# GrblMainboard_-_v2_2.net
KiCad netlist of a schematic drawn in EAGLE
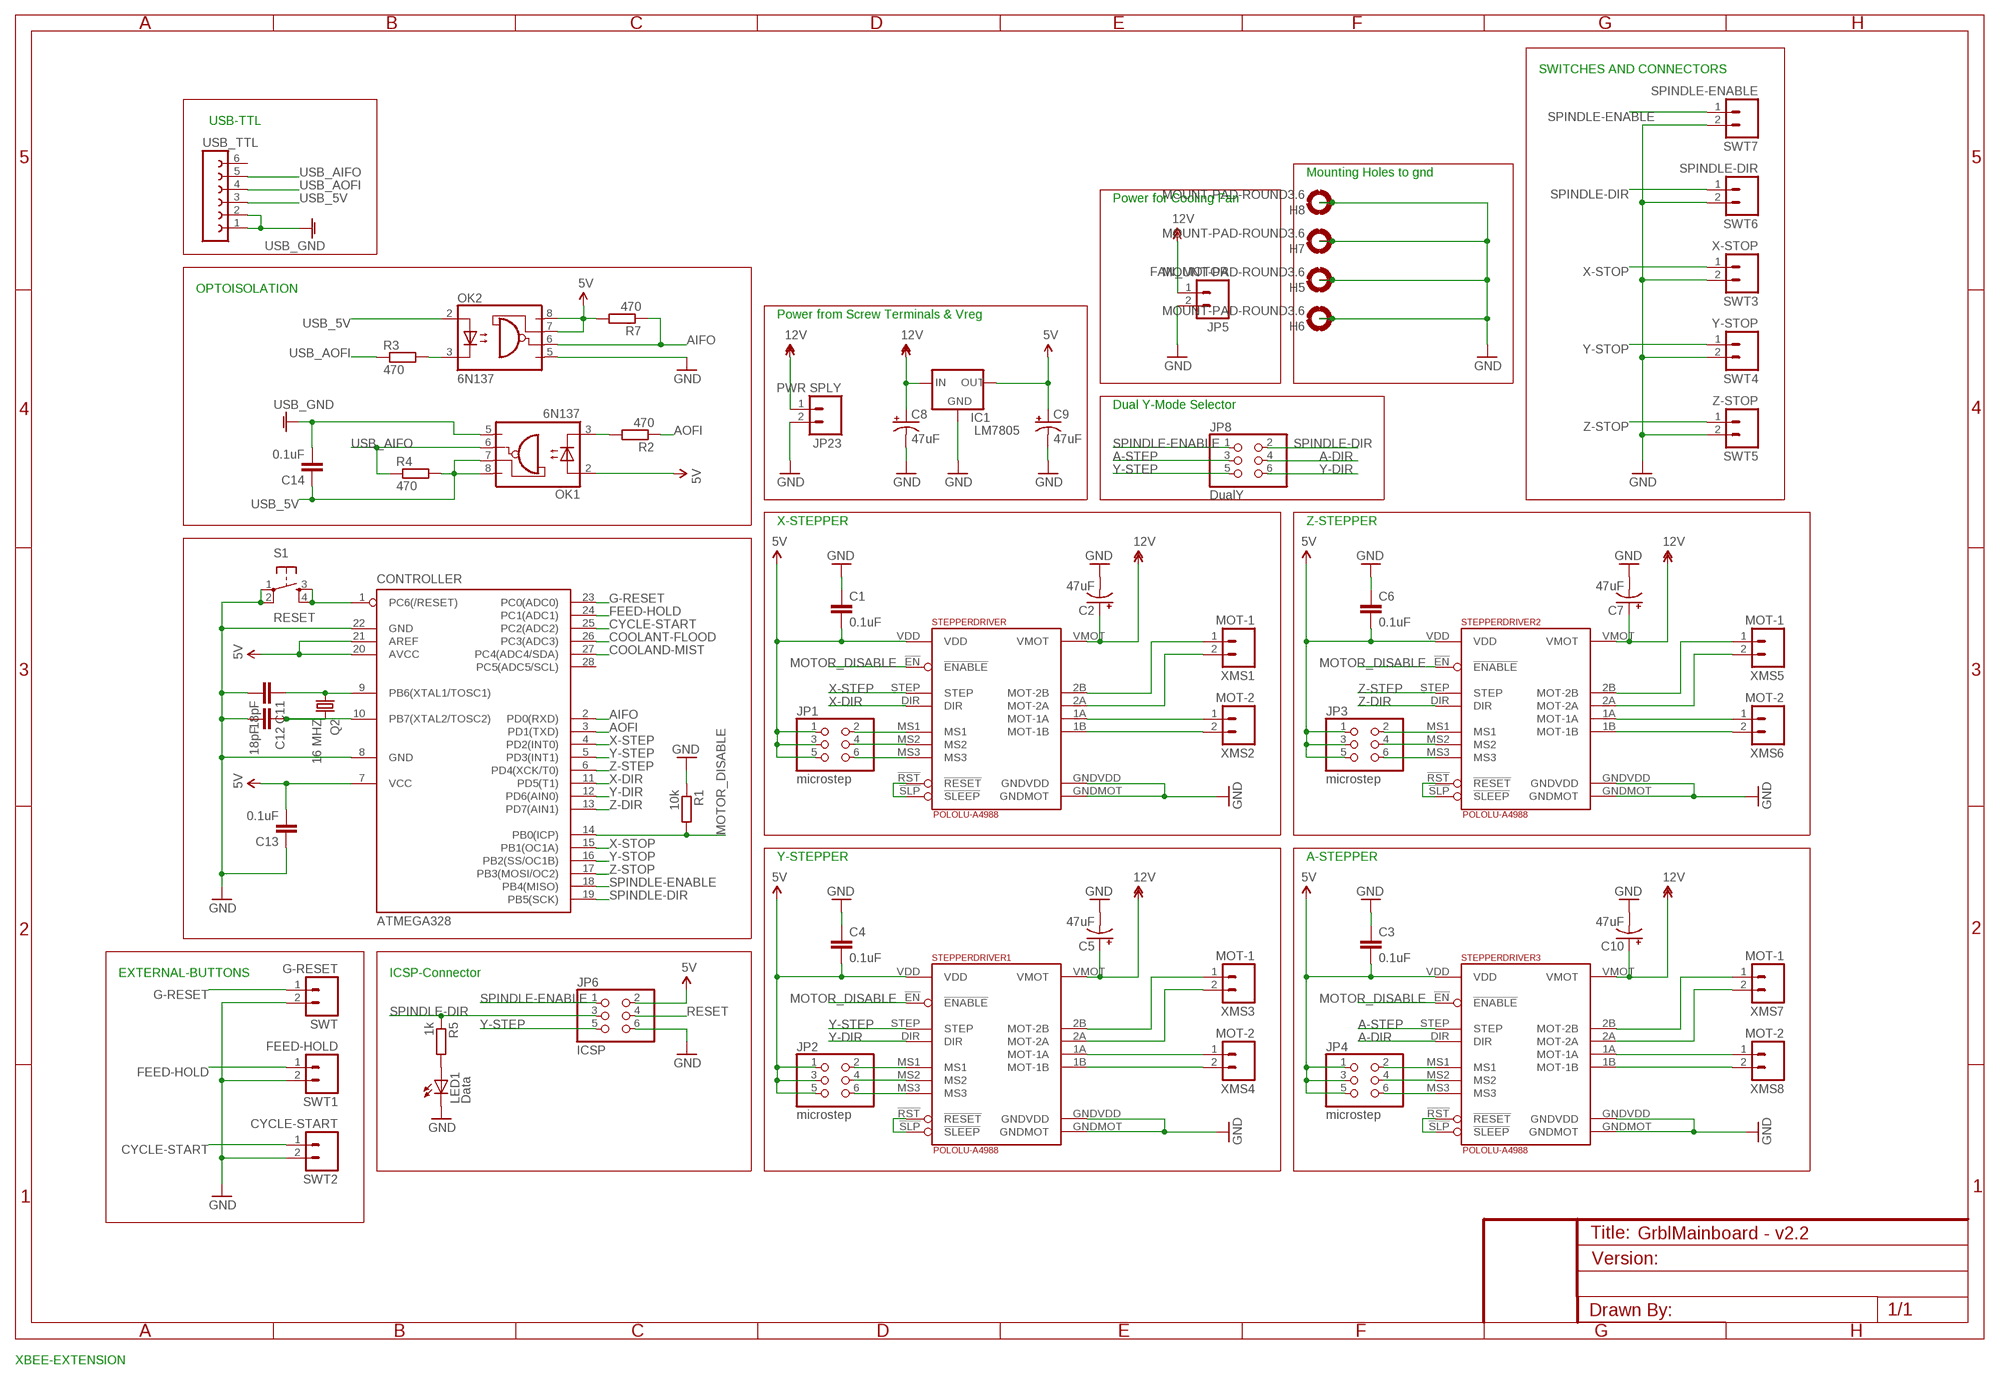
[diagram p0: schematic, sheet 1]

(export (version "E")
  (design (tool "Eeschema 10.0.6"))
  (components
    (comp (ref "ATMEGA328")
      (value "CONTROLLER")
      (footprint "eagle-import:DIL28-3")
      (libsource (lib "eagle-import") (part "MEGA8-P"))
    )
    (comp (ref "C1")
      (value "0.1uF")
      (footprint "eagle-import:C025-025X050")
      (libsource (lib "eagle-import") (part "C-EU025-025X050"))
    )
    (comp (ref "C2")
      (value "47uF")
      (footprint "eagle-import:E2,5-6")
      (libsource (lib "eagle-import") (part "CPOL-USE2.5-6"))
    )
    (comp (ref "C3")
      (value "0.1uF")
      (footprint "eagle-import:C025-025X050")
      (libsource (lib "eagle-import") (part "C-EU025-025X050"))
    )
    (comp (ref "C4")
      (value "0.1uF")
      (footprint "eagle-import:C025-025X050")
      (libsource (lib "eagle-import") (part "C-EU025-025X050"))
    )
    (comp (ref "C5")
      (value "47uF")
      (footprint "eagle-import:E2,5-6")
      (libsource (lib "eagle-import") (part "CPOL-USE2.5-6"))
    )
    (comp (ref "C6")
      (value "0.1uF")
      (footprint "eagle-import:C025-025X050")
      (libsource (lib "eagle-import") (part "C-EU025-025X050"))
    )
    (comp (ref "C7")
      (value "47uF")
      (footprint "eagle-import:E2,5-6")
      (libsource (lib "eagle-import") (part "CPOL-USE2.5-6"))
    )
    (comp (ref "C8")
      (value "47uF")
      (footprint "eagle-import:E2,5-6")
      (libsource (lib "eagle-import") (part "CPOL-USE2.5-6"))
    )
    (comp (ref "C9")
      (value "47uF")
      (footprint "eagle-import:E2,5-6")
      (libsource (lib "eagle-import") (part "CPOL-USE2.5-6"))
    )
    (comp (ref "C10")
      (value "47uF")
      (footprint "eagle-import:E2,5-6")
      (libsource (lib "eagle-import") (part "CPOL-USE2.5-6"))
    )
    (comp (ref "C11")
      (value "18pF")
      (footprint "eagle-import:CAP-PTH-SMALL2")
      (libsource (lib "eagle-import") (part "CAPPTH2"))
    )
    (comp (ref "C12")
      (value "18pF")
      (footprint "eagle-import:CAP-PTH-SMALL2")
      (libsource (lib "eagle-import") (part "CAPPTH2"))
    )
    (comp (ref "C13")
      (value "0.1uF")
      (footprint "eagle-import:CAP-PTH-SMALL2")
      (libsource (lib "eagle-import") (part "CAPPTH2"))
    )
    (comp (ref "C14")
      (value "0.1uF")
      (footprint "eagle-import:CAP-PTH-SMALL2")
      (libsource (lib "eagle-import") (part "CAPPTH2"))
    )
    (comp (ref "H5")
      (value "MOUNT-PAD-ROUND3.6")
      (footprint "eagle-import:3,6-PAD")
      (libsource (lib "eagle-import") (part "MOUNT-PAD-ROUND3.6"))
    )
    (comp (ref "H6")
      (value "MOUNT-PAD-ROUND3.6")
      (footprint "eagle-import:3,6-PAD")
      (libsource (lib "eagle-import") (part "MOUNT-PAD-ROUND3.6"))
    )
    (comp (ref "H7")
      (value "MOUNT-PAD-ROUND3.6")
      (footprint "eagle-import:3,6-PAD")
      (libsource (lib "eagle-import") (part "MOUNT-PAD-ROUND3.6"))
    )
    (comp (ref "H8")
      (value "MOUNT-PAD-ROUND3.6")
      (footprint "eagle-import:3,6-PAD")
      (libsource (lib "eagle-import") (part "MOUNT-PAD-ROUND3.6"))
    )
    (comp (ref "IC1")
      (value "LM7805")
      (footprint "eagle-import:78XXL-CUSTOM")
      (libsource (lib "eagle-import") (part "V_REG_78XX"))
    )
    (comp (ref "JP1")
      (value "microstep")
      (footprint "eagle-import:2X03")
      (libsource (lib "eagle-import") (part "PINHD-2X3"))
    )
    (comp (ref "JP2")
      (value "microstep")
      (footprint "eagle-import:2X03")
      (libsource (lib "eagle-import") (part "PINHD-2X3"))
    )
    (comp (ref "JP3")
      (value "microstep")
      (footprint "eagle-import:2X03")
      (libsource (lib "eagle-import") (part "PINHD-2X3"))
    )
    (comp (ref "JP4")
      (value "microstep")
      (footprint "eagle-import:2X03")
      (libsource (lib "eagle-import") (part "PINHD-2X3"))
    )
    (comp (ref "JP5")
      (value "FAN_MOTOR")
      (footprint "eagle-import:SCREWTERMINAL-5MM-2")
      (libsource (lib "eagle-import") (part "M025MM"))
    )
    (comp (ref "JP6")
      (value "ICSP")
      (footprint "eagle-import:2X03")
      (libsource (lib "eagle-import") (part "PINHD-2X3"))
    )
    (comp (ref "JP8")
      (value "DualY")
      (footprint "eagle-import:2X03")
      (libsource (lib "eagle-import") (part "PINHD-2X3"))
    )
    (comp (ref "JP23")
      (value "PWR SPLY")
      (footprint "eagle-import:SCREWTERMINAL-5MM-2")
      (libsource (lib "eagle-import") (part "M025MM"))
    )
    (comp (ref "LED1")
      (value "Data")
      (footprint "eagle-import:LED5MM")
      (libsource (lib "eagle-import") (part "LED5MM"))
    )
    (comp (ref "OK1")
      (value "6N137")
      (footprint "eagle-import:DIL08")
      (libsource (lib "eagle-import") (part "6N137"))
    )
    (comp (ref "OK2")
      (value "6N137")
      (footprint "eagle-import:DIL08")
      (libsource (lib "eagle-import") (part "6N137"))
    )
    (comp (ref "Q2")
      (value "16 MHZ")
      (footprint "eagle-import:HC49_S")
      (libsource (lib "eagle-import") (part "CRYSTALHC49S"))
    )
    (comp (ref "R1")
      (value "10k")
      (footprint "eagle-import:0207_10")
      (libsource (lib "eagle-import") (part "R-EU_0207/10"))
    )
    (comp (ref "R2")
      (value "470")
      (footprint "eagle-import:0207_12")
      (libsource (lib "eagle-import") (part "R-EU_0207/12"))
    )
    (comp (ref "R3")
      (value "470")
      (footprint "eagle-import:0207_12")
      (libsource (lib "eagle-import") (part "R-EU_0207/12"))
    )
    (comp (ref "R4")
      (value "470")
      (footprint "eagle-import:0207_12")
      (libsource (lib "eagle-import") (part "R-EU_0207/12"))
    )
    (comp (ref "R5")
      (value "1k")
      (footprint "eagle-import:0207_10")
      (libsource (lib "eagle-import") (part "R-EU_0207/10"))
    )
    (comp (ref "R7")
      (value "470")
      (footprint "eagle-import:0207_12")
      (libsource (lib "eagle-import") (part "R-EU_0207/12"))
    )
    (comp (ref "S1")
      (value "RESET")
      (footprint "eagle-import:TACTILE-PTH")
      (libsource (lib "eagle-import") (part "TAC_SWITCHPTH"))
    )
    (comp (ref "STEPPERDRIVER")
      (value "POLOLU-A4988")
      (footprint "eagle-import:POLOLU-ALLEGRO-PTH")
      (libsource (lib "eagle-import") (part "POLOLU-ALLEGRO"))
    )
    (comp (ref "STEPPERDRIVER1")
      (value "POLOLU-A4988")
      (footprint "eagle-import:POLOLU-ALLEGRO-PTH")
      (libsource (lib "eagle-import") (part "POLOLU-ALLEGRO"))
    )
    (comp (ref "STEPPERDRIVER2")
      (value "POLOLU-A4988")
      (footprint "eagle-import:POLOLU-ALLEGRO-PTH")
      (libsource (lib "eagle-import") (part "POLOLU-ALLEGRO"))
    )
    (comp (ref "STEPPERDRIVER3")
      (value "POLOLU-A4988")
      (footprint "eagle-import:POLOLU-ALLEGRO-PTH")
      (libsource (lib "eagle-import") (part "POLOLU-ALLEGRO"))
    )
    (comp (ref "SWT")
      (value "G-RESET")
      (footprint "eagle-import:SCREWTERMINAL-5MM-2")
      (libsource (lib "eagle-import") (part "M025MM"))
    )
    (comp (ref "SWT1")
      (value "FEED-HOLD")
      (footprint "eagle-import:SCREWTERMINAL-5MM-2")
      (libsource (lib "eagle-import") (part "M025MM"))
    )
    (comp (ref "SWT2")
      (value "CYCLE-START")
      (footprint "eagle-import:SCREWTERMINAL-5MM-2")
      (libsource (lib "eagle-import") (part "M025MM"))
    )
    (comp (ref "SWT3")
      (value "X-STOP")
      (footprint "eagle-import:SCREWTERMINAL-5MM-2")
      (libsource (lib "eagle-import") (part "M025MM"))
    )
    (comp (ref "SWT4")
      (value "Y-STOP")
      (footprint "eagle-import:SCREWTERMINAL-5MM-2")
      (libsource (lib "eagle-import") (part "M025MM"))
    )
    (comp (ref "SWT5")
      (value "Z-STOP")
      (footprint "eagle-import:SCREWTERMINAL-5MM-2")
      (libsource (lib "eagle-import") (part "M025MM"))
    )
    (comp (ref "SWT6")
      (value "SPINDLE-DIR")
      (footprint "eagle-import:SCREWTERMINAL-5MM-2")
      (libsource (lib "eagle-import") (part "M025MM"))
    )
    (comp (ref "SWT7")
      (value "SPINDLE-ENABLE")
      (footprint "eagle-import:SCREWTERMINAL-5MM-2")
      (libsource (lib "eagle-import") (part "M025MM"))
    )
    (comp (ref "USB_TTL")
      (value "FE06-1")
      (footprint "eagle-import:FE06")
      (libsource (lib "eagle-import") (part "FE06-1"))
    )
    (comp (ref "XMS1")
      (value "MOT-1")
      (footprint "eagle-import:SCREWTERMINAL-5MM-2")
      (libsource (lib "eagle-import") (part "M025MM"))
    )
    (comp (ref "XMS2")
      (value "MOT-2")
      (footprint "eagle-import:SCREWTERMINAL-5MM-2")
      (libsource (lib "eagle-import") (part "M025MM"))
    )
    (comp (ref "XMS3")
      (value "MOT-1")
      (footprint "eagle-import:SCREWTERMINAL-5MM-2")
      (libsource (lib "eagle-import") (part "M025MM"))
    )
    (comp (ref "XMS4")
      (value "MOT-2")
      (footprint "eagle-import:SCREWTERMINAL-5MM-2")
      (libsource (lib "eagle-import") (part "M025MM"))
    )
    (comp (ref "XMS5")
      (value "MOT-1")
      (footprint "eagle-import:SCREWTERMINAL-5MM-2")
      (libsource (lib "eagle-import") (part "M025MM"))
    )
    (comp (ref "XMS6")
      (value "MOT-2")
      (footprint "eagle-import:SCREWTERMINAL-5MM-2")
      (libsource (lib "eagle-import") (part "M025MM"))
    )
    (comp (ref "XMS7")
      (value "MOT-1")
      (footprint "eagle-import:SCREWTERMINAL-5MM-2")
      (libsource (lib "eagle-import") (part "M025MM"))
    )
    (comp (ref "XMS8")
      (value "MOT-2")
      (footprint "eagle-import:SCREWTERMINAL-5MM-2")
      (libsource (lib "eagle-import") (part "M025MM"))
    )
  )
  (nets
    (net (code "1") (name "/A-DIR") (class "Default")
      (node (ref "JP8") (pin "4") (pinfunction "4_4") (pintype "passive"))
      (node (ref "STEPPERDRIVER3") (pin "DIR") (pinfunction "DIR_DIR") (pintype "bidirectional"))
    )
    (net (code "2") (name "/A-STEP") (class "Default")
      (node (ref "JP8") (pin "3") (pinfunction "3_3") (pintype "passive"))
      (node (ref "STEPPERDRIVER3") (pin "STEP") (pinfunction "STEP_STEP") (pintype "bidirectional"))
    )
    (net (code "3") (name "/AIFO") (class "Default")
      (node (ref "ATMEGA328") (pin "2") (pinfunction "PD0(RXD)_2") (pintype "bidirectional"))
      (node (ref "OK2") (pin "6") (pinfunction "VO_6") (pintype "passive"))
      (node (ref "R7") (pin "1") (pinfunction "1_1") (pintype "passive"))
    )
    (net (code "4") (name "/AOFI") (class "Default")
      (node (ref "ATMEGA328") (pin "3") (pinfunction "PD1(TXD)_3") (pintype "bidirectional"))
      (node (ref "R2") (pin "1") (pinfunction "1_1") (pintype "passive"))
    )
    (net (code "5") (name "/COOLAND-MIST") (class "Default")
      (node (ref "ATMEGA328") (pin "27") (pinfunction "PC4(ADC4/SDA)_27") (pintype "bidirectional"))
    )
    (net (code "6") (name "/COOLANT-FLOOD") (class "Default")
      (node (ref "ATMEGA328") (pin "26") (pinfunction "PC3(ADC3)_26") (pintype "bidirectional"))
    )
    (net (code "7") (name "/CYCLE-START") (class "Default")
      (node (ref "ATMEGA328") (pin "25") (pinfunction "PC2(ADC2)_25") (pintype "bidirectional"))
      (node (ref "SWT2") (pin "1") (pinfunction "1_1") (pintype "passive"))
    )
    (net (code "8") (name "/FEED-HOLD") (class "Default")
      (node (ref "ATMEGA328") (pin "24") (pinfunction "PC1(ADC1)_24") (pintype "bidirectional"))
      (node (ref "SWT1") (pin "1") (pinfunction "1_1") (pintype "passive"))
    )
    (net (code "9") (name "/G-RESET") (class "Default")
      (node (ref "ATMEGA328") (pin "23") (pinfunction "PC0(ADC0)_23") (pintype "bidirectional"))
      (node (ref "SWT") (pin "1") (pinfunction "1_1") (pintype "passive"))
    )
    (net (code "10") (name "/MOTOR_DISABLE") (class "Default")
      (node (ref "ATMEGA328") (pin "14") (pinfunction "PB0(ICP)_14") (pintype "bidirectional"))
      (node (ref "R1") (pin "2") (pinfunction "2_2") (pintype "passive"))
      (node (ref "STEPPERDRIVER") (pin "!EN") (pinfunction "~{ENABLE}_!EN") (pintype "input"))
      (node (ref "STEPPERDRIVER1") (pin "!EN") (pinfunction "~{ENABLE}_!EN") (pintype "input"))
      (node (ref "STEPPERDRIVER2") (pin "!EN") (pinfunction "~{ENABLE}_!EN") (pintype "input"))
      (node (ref "STEPPERDRIVER3") (pin "!EN") (pinfunction "~{ENABLE}_!EN") (pintype "input"))
    )
    (net (code "11") (name "/RESET") (class "Default")
      (node (ref "ATMEGA328") (pin "1") (pinfunction "PC6(/RESET)_1") (pintype "bidirectional"))
      (node (ref "JP6") (pin "4") (pinfunction "4_4") (pintype "passive"))
      (node (ref "S1") (pin "3") (pinfunction "3_3") (pintype "passive"))
      (node (ref "S1") (pin "4") (pinfunction "4_4") (pintype "passive"))
    )
    (net (code "12") (name "/SPINDLE-DIR") (class "Default")
      (node (ref "ATMEGA328") (pin "19") (pinfunction "PB5(SCK)_19") (pintype "bidirectional"))
      (node (ref "JP6") (pin "3") (pinfunction "3_3") (pintype "passive"))
      (node (ref "JP8") (pin "2") (pinfunction "2_2") (pintype "passive"))
      (node (ref "R5") (pin "1") (pinfunction "1_1") (pintype "passive"))
      (node (ref "SWT6") (pin "1") (pinfunction "1_1") (pintype "passive"))
    )
    (net (code "13") (name "/SPINDLE-ENABLE") (class "Default")
      (node (ref "ATMEGA328") (pin "18") (pinfunction "PB4(MISO)_18") (pintype "bidirectional"))
      (node (ref "JP6") (pin "1") (pinfunction "1_1") (pintype "passive"))
      (node (ref "JP8") (pin "1") (pinfunction "1_1") (pintype "passive"))
      (node (ref "SWT7") (pin "1") (pinfunction "1_1") (pintype "passive"))
    )
    (net (code "14") (name "/USB_5V") (class "Default")
      (node (ref "C14") (pin "1") (pinfunction "1_1") (pintype "passive"))
      (node (ref "OK1") (pin "7") (pinfunction "VE_7") (pintype "passive"))
      (node (ref "OK1") (pin "8") (pinfunction "VCC_8") (pintype "passive"))
      (node (ref "OK2") (pin "2") (pinfunction "A_2") (pintype "passive"))
      (node (ref "R4") (pin "2") (pinfunction "2_2") (pintype "passive"))
      (node (ref "USB_TTL") (pin "3") (pinfunction "3_3") (pintype "passive"))
    )
    (net (code "15") (name "/USB_AIFO") (class "Default")
      (node (ref "OK1") (pin "6") (pinfunction "VO_6") (pintype "passive"))
      (node (ref "R4") (pin "1") (pinfunction "1_1") (pintype "passive"))
      (node (ref "USB_TTL") (pin "5") (pinfunction "5_5") (pintype "passive"))
    )
    (net (code "16") (name "/USB_AOFI") (class "Default")
      (node (ref "R3") (pin "1") (pinfunction "1_1") (pintype "passive"))
      (node (ref "USB_TTL") (pin "4") (pinfunction "4_4") (pintype "passive"))
    )
    (net (code "17") (name "/X-DIR") (class "Default")
      (node (ref "ATMEGA328") (pin "11") (pinfunction "PD5(T1)_11") (pintype "bidirectional"))
      (node (ref "STEPPERDRIVER") (pin "DIR") (pinfunction "DIR_DIR") (pintype "bidirectional"))
    )
    (net (code "18") (name "/X-STEP") (class "Default")
      (node (ref "ATMEGA328") (pin "4") (pinfunction "PD2(INT0)_4") (pintype "bidirectional"))
      (node (ref "STEPPERDRIVER") (pin "STEP") (pinfunction "STEP_STEP") (pintype "bidirectional"))
    )
    (net (code "19") (name "/X-STOP") (class "Default")
      (node (ref "ATMEGA328") (pin "15") (pinfunction "PB1(OC1A)_15") (pintype "bidirectional"))
      (node (ref "SWT3") (pin "1") (pinfunction "1_1") (pintype "passive"))
    )
    (net (code "20") (name "/Y-DIR") (class "Default")
      (node (ref "ATMEGA328") (pin "12") (pinfunction "PD6(AIN0)_12") (pintype "bidirectional"))
      (node (ref "JP8") (pin "6") (pinfunction "6_6") (pintype "passive"))
      (node (ref "STEPPERDRIVER1") (pin "DIR") (pinfunction "DIR_DIR") (pintype "bidirectional"))
    )
    (net (code "21") (name "/Y-STEP") (class "Default")
      (node (ref "ATMEGA328") (pin "5") (pinfunction "PD3(INT1)_5") (pintype "bidirectional"))
      (node (ref "JP6") (pin "5") (pinfunction "5_5") (pintype "passive"))
      (node (ref "JP8") (pin "5") (pinfunction "5_5") (pintype "passive"))
      (node (ref "STEPPERDRIVER1") (pin "STEP") (pinfunction "STEP_STEP") (pintype "bidirectional"))
    )
    (net (code "22") (name "/Y-STOP") (class "Default")
      (node (ref "ATMEGA328") (pin "16") (pinfunction "PB2(SS/OC1B)_16") (pintype "bidirectional"))
      (node (ref "SWT4") (pin "1") (pinfunction "1_1") (pintype "passive"))
    )
    (net (code "23") (name "/Z-DIR") (class "Default")
      (node (ref "ATMEGA328") (pin "13") (pinfunction "PD7(AIN1)_13") (pintype "bidirectional"))
      (node (ref "STEPPERDRIVER2") (pin "DIR") (pinfunction "DIR_DIR") (pintype "bidirectional"))
    )
    (net (code "24") (name "/Z-STEP") (class "Default")
      (node (ref "ATMEGA328") (pin "6") (pinfunction "PD4(XCK/T0)_6") (pintype "bidirectional"))
      (node (ref "STEPPERDRIVER2") (pin "STEP") (pinfunction "STEP_STEP") (pintype "bidirectional"))
    )
    (net (code "25") (name "/Z-STOP") (class "Default")
      (node (ref "ATMEGA328") (pin "17") (pinfunction "PB3(MOSI/OC2)_17") (pintype "bidirectional"))
      (node (ref "SWT5") (pin "1") (pinfunction "1_1") (pintype "passive"))
    )
    (net (code "26") (name "5V") (class "Default")
      (node (ref "ATMEGA328") (pin "20") (pinfunction "AVCC_20") (pintype "power_in"))
      (node (ref "ATMEGA328") (pin "21") (pinfunction "AREF_21") (pintype "passive"))
      (node (ref "ATMEGA328") (pin "7") (pinfunction "VCC_7") (pintype "power_in"))
      (node (ref "C1") (pin "2") (pinfunction "2_2") (pintype "passive"))
      (node (ref "C13") (pin "2") (pinfunction "2_2") (pintype "passive"))
      (node (ref "C3") (pin "2") (pinfunction "2_2") (pintype "passive"))
      (node (ref "C4") (pin "2") (pinfunction "2_2") (pintype "passive"))
      (node (ref "C6") (pin "2") (pinfunction "2_2") (pintype "passive"))
      (node (ref "C9") (pin "+") (pinfunction "+_+") (pintype "passive"))
      (node (ref "IC1") (pin "OUT") (pinfunction "OUT_OUT") (pintype "output"))
      (node (ref "JP1") (pin "1") (pinfunction "1_1") (pintype "passive"))
      (node (ref "JP1") (pin "3") (pinfunction "3_3") (pintype "passive"))
      (node (ref "JP1") (pin "5") (pinfunction "5_5") (pintype "passive"))
      (node (ref "JP2") (pin "1") (pinfunction "1_1") (pintype "passive"))
      (node (ref "JP2") (pin "3") (pinfunction "3_3") (pintype "passive"))
      (node (ref "JP2") (pin "5") (pinfunction "5_5") (pintype "passive"))
      (node (ref "JP3") (pin "1") (pinfunction "1_1") (pintype "passive"))
      (node (ref "JP3") (pin "3") (pinfunction "3_3") (pintype "passive"))
      (node (ref "JP3") (pin "5") (pinfunction "5_5") (pintype "passive"))
      (node (ref "JP4") (pin "1") (pinfunction "1_1") (pintype "passive"))
      (node (ref "JP4") (pin "3") (pinfunction "3_3") (pintype "passive"))
      (node (ref "JP4") (pin "5") (pinfunction "5_5") (pintype "passive"))
      (node (ref "JP6") (pin "2") (pinfunction "2_2") (pintype "passive"))
      (node (ref "OK1") (pin "2") (pinfunction "A_2") (pintype "passive"))
      (node (ref "OK2") (pin "7") (pinfunction "VE_7") (pintype "passive"))
      (node (ref "OK2") (pin "8") (pinfunction "VCC_8") (pintype "passive"))
      (node (ref "R7") (pin "2") (pinfunction "2_2") (pintype "passive"))
      (node (ref "STEPPERDRIVER") (pin "VDD") (pinfunction "VDD_VDD") (pintype "power_in"))
      (node (ref "STEPPERDRIVER1") (pin "VDD") (pinfunction "VDD_VDD") (pintype "power_in"))
      (node (ref "STEPPERDRIVER2") (pin "VDD") (pinfunction "VDD_VDD") (pintype "power_in"))
      (node (ref "STEPPERDRIVER3") (pin "VDD") (pinfunction "VDD_VDD") (pintype "power_in"))
    )
    (net (code "27") (name "12V") (class "Default")
      (node (ref "C10") (pin "+") (pinfunction "+_+") (pintype "passive"))
      (node (ref "C2") (pin "+") (pinfunction "+_+") (pintype "passive"))
      (node (ref "C5") (pin "+") (pinfunction "+_+") (pintype "passive"))
      (node (ref "C7") (pin "+") (pinfunction "+_+") (pintype "passive"))
      (node (ref "C8") (pin "+") (pinfunction "+_+") (pintype "passive"))
      (node (ref "IC1") (pin "IN") (pinfunction "IN_IN") (pintype "input"))
      (node (ref "JP23") (pin "1") (pinfunction "1_1") (pintype "passive"))
      (node (ref "JP5") (pin "1") (pinfunction "1_1") (pintype "passive"))
      (node (ref "STEPPERDRIVER") (pin "VMOT") (pinfunction "VMOT_VMOT") (pintype "power_in"))
      (node (ref "STEPPERDRIVER1") (pin "VMOT") (pinfunction "VMOT_VMOT") (pintype "power_in"))
      (node (ref "STEPPERDRIVER2") (pin "VMOT") (pinfunction "VMOT_VMOT") (pintype "power_in"))
      (node (ref "STEPPERDRIVER3") (pin "VMOT") (pinfunction "VMOT_VMOT") (pintype "power_in"))
    )
    (net (code "28") (name "GND") (class "Default")
      (node (ref "ATMEGA328") (pin "22") (pinfunction "GND_22") (pintype "power_in"))
      (node (ref "ATMEGA328") (pin "8") (pinfunction "GND_8") (pintype "power_in"))
      (node (ref "C1") (pin "1") (pinfunction "1_1") (pintype "passive"))
      (node (ref "C10") (pin "-") (pinfunction "-_-") (pintype "passive"))
      (node (ref "C11") (pin "2") (pinfunction "2_2") (pintype "passive"))
      (node (ref "C12") (pin "2") (pinfunction "2_2") (pintype "passive"))
      (node (ref "C13") (pin "1") (pinfunction "1_1") (pintype "passive"))
      (node (ref "C2") (pin "-") (pinfunction "-_-") (pintype "passive"))
      (node (ref "C3") (pin "1") (pinfunction "1_1") (pintype "passive"))
      (node (ref "C4") (pin "1") (pinfunction "1_1") (pintype "passive"))
      (node (ref "C5") (pin "-") (pinfunction "-_-") (pintype "passive"))
      (node (ref "C6") (pin "1") (pinfunction "1_1") (pintype "passive"))
      (node (ref "C7") (pin "-") (pinfunction "-_-") (pintype "passive"))
      (node (ref "C8") (pin "-") (pinfunction "-_-") (pintype "passive"))
      (node (ref "C9") (pin "-") (pinfunction "-_-") (pintype "passive"))
      (node (ref "H5") (pin "B3,6") (pinfunction "MOUNT_B3,6") (pintype "passive"))
      (node (ref "H6") (pin "B3,6") (pinfunction "MOUNT_B3,6") (pintype "passive"))
      (node (ref "H7") (pin "B3,6") (pinfunction "MOUNT_B3,6") (pintype "passive"))
      (node (ref "H8") (pin "B3,6") (pinfunction "MOUNT_B3,6") (pintype "passive"))
      (node (ref "IC1") (pin "GND") (pinfunction "GND_GND") (pintype "input"))
      (node (ref "JP23") (pin "2") (pinfunction "2_2") (pintype "passive"))
      (node (ref "JP5") (pin "2") (pinfunction "2_2") (pintype "passive"))
      (node (ref "JP6") (pin "6") (pinfunction "6_6") (pintype "passive"))
      (node (ref "LED1") (pin "K") (pinfunction "C_K") (pintype "passive"))
      (node (ref "OK2") (pin "5") (pinfunction "GND_5") (pintype "passive"))
      (node (ref "R1") (pin "1") (pinfunction "1_1") (pintype "passive"))
      (node (ref "S1") (pin "1") (pinfunction "1_1") (pintype "passive"))
      (node (ref "S1") (pin "2") (pinfunction "2_2") (pintype "passive"))
      (node (ref "STEPPERDRIVER") (pin "GNDMOT") (pinfunction "GNDMOT_GNDMOT") (pintype "power_in"))
      (node (ref "STEPPERDRIVER") (pin "GNDVDD") (pinfunction "GNDVDD_GNDVDD") (pintype "power_in"))
      (node (ref "STEPPERDRIVER1") (pin "GNDMOT") (pinfunction "GNDMOT_GNDMOT") (pintype "power_in"))
      (node (ref "STEPPERDRIVER1") (pin "GNDVDD") (pinfunction "GNDVDD_GNDVDD") (pintype "power_in"))
      (node (ref "STEPPERDRIVER2") (pin "GNDMOT") (pinfunction "GNDMOT_GNDMOT") (pintype "power_in"))
      (node (ref "STEPPERDRIVER2") (pin "GNDVDD") (pinfunction "GNDVDD_GNDVDD") (pintype "power_in"))
      (node (ref "STEPPERDRIVER3") (pin "GNDMOT") (pinfunction "GNDMOT_GNDMOT") (pintype "power_in"))
      (node (ref "STEPPERDRIVER3") (pin "GNDVDD") (pinfunction "GNDVDD_GNDVDD") (pintype "power_in"))
      (node (ref "SWT") (pin "2") (pinfunction "2_2") (pintype "passive"))
      (node (ref "SWT1") (pin "2") (pinfunction "2_2") (pintype "passive"))
      (node (ref "SWT2") (pin "2") (pinfunction "2_2") (pintype "passive"))
      (node (ref "SWT3") (pin "2") (pinfunction "2_2") (pintype "passive"))
      (node (ref "SWT4") (pin "2") (pinfunction "2_2") (pintype "passive"))
      (node (ref "SWT5") (pin "2") (pinfunction "2_2") (pintype "passive"))
      (node (ref "SWT6") (pin "2") (pinfunction "2_2") (pintype "passive"))
      (node (ref "SWT7") (pin "2") (pinfunction "2_2") (pintype "passive"))
    )
    (net (code "29") (name "Net-(ATMEGA328-PB6(XTAL1{slash}TOSC1))") (class "Default")
      (node (ref "ATMEGA328") (pin "9") (pinfunction "PB6(XTAL1/TOSC1)_9") (pintype "bidirectional"))
      (node (ref "C11") (pin "1") (pinfunction "1_1") (pintype "passive"))
      (node (ref "Q2") (pin "1") (pinfunction "1_1") (pintype "passive"))
    )
    (net (code "30") (name "Net-(ATMEGA328-PB7(XTAL2{slash}TOSC2))") (class "Default")
      (node (ref "ATMEGA328") (pin "10") (pinfunction "PB7(XTAL2/TOSC2)_10") (pintype "bidirectional"))
      (node (ref "C12") (pin "1") (pinfunction "1_1") (pintype "passive"))
      (node (ref "Q2") (pin "2") (pinfunction "2_2") (pintype "passive"))
    )
    (net (code "31") (name "Net-(JP1-Pad2)") (class "Default")
      (node (ref "JP1") (pin "2") (pinfunction "2_2") (pintype "passive"))
      (node (ref "STEPPERDRIVER") (pin "MS1") (pinfunction "MS1_MS1") (pintype "input"))
    )
    (net (code "32") (name "Net-(JP1-Pad4)") (class "Default")
      (node (ref "JP1") (pin "4") (pinfunction "4_4") (pintype "passive"))
      (node (ref "STEPPERDRIVER") (pin "MS2") (pinfunction "MS2_MS2") (pintype "input"))
    )
    (net (code "33") (name "Net-(JP1-Pad6)") (class "Default")
      (node (ref "JP1") (pin "6") (pinfunction "6_6") (pintype "passive"))
      (node (ref "STEPPERDRIVER") (pin "MS3") (pinfunction "MS3_MS3") (pintype "input"))
    )
    (net (code "34") (name "Net-(JP2-Pad2)") (class "Default")
      (node (ref "JP2") (pin "2") (pinfunction "2_2") (pintype "passive"))
      (node (ref "STEPPERDRIVER1") (pin "MS1") (pinfunction "MS1_MS1") (pintype "input"))
    )
    (net (code "35") (name "Net-(JP2-Pad4)") (class "Default")
      (node (ref "JP2") (pin "4") (pinfunction "4_4") (pintype "passive"))
      (node (ref "STEPPERDRIVER1") (pin "MS2") (pinfunction "MS2_MS2") (pintype "input"))
    )
    (net (code "36") (name "Net-(JP2-Pad6)") (class "Default")
      (node (ref "JP2") (pin "6") (pinfunction "6_6") (pintype "passive"))
      (node (ref "STEPPERDRIVER1") (pin "MS3") (pinfunction "MS3_MS3") (pintype "input"))
    )
    (net (code "37") (name "Net-(JP3-Pad2)") (class "Default")
      (node (ref "JP3") (pin "2") (pinfunction "2_2") (pintype "passive"))
      (node (ref "STEPPERDRIVER2") (pin "MS1") (pinfunction "MS1_MS1") (pintype "input"))
    )
    (net (code "38") (name "Net-(JP3-Pad4)") (class "Default")
      (node (ref "JP3") (pin "4") (pinfunction "4_4") (pintype "passive"))
      (node (ref "STEPPERDRIVER2") (pin "MS2") (pinfunction "MS2_MS2") (pintype "input"))
    )
    (net (code "39") (name "Net-(JP3-Pad6)") (class "Default")
      (node (ref "JP3") (pin "6") (pinfunction "6_6") (pintype "passive"))
      (node (ref "STEPPERDRIVER2") (pin "MS3") (pinfunction "MS3_MS3") (pintype "input"))
    )
    (net (code "40") (name "Net-(JP4-Pad2)") (class "Default")
      (node (ref "JP4") (pin "2") (pinfunction "2_2") (pintype "passive"))
      (node (ref "STEPPERDRIVER3") (pin "MS1") (pinfunction "MS1_MS1") (pintype "input"))
    )
    (net (code "41") (name "Net-(JP4-Pad4)") (class "Default")
      (node (ref "JP4") (pin "4") (pinfunction "4_4") (pintype "passive"))
      (node (ref "STEPPERDRIVER3") (pin "MS2") (pinfunction "MS2_MS2") (pintype "input"))
    )
    (net (code "42") (name "Net-(JP4-Pad6)") (class "Default")
      (node (ref "JP4") (pin "6") (pinfunction "6_6") (pintype "passive"))
      (node (ref "STEPPERDRIVER3") (pin "MS3") (pinfunction "MS3_MS3") (pintype "input"))
    )
    (net (code "43") (name "Net-(LED1-PadA)") (class "Default")
      (node (ref "LED1") (pin "A") (pinfunction "A_A") (pintype "passive"))
      (node (ref "R5") (pin "2") (pinfunction "2_2") (pintype "passive"))
    )
    (net (code "44") (name "Net-(OK1-C)") (class "Default")
      (node (ref "OK1") (pin "3") (pinfunction "C_3") (pintype "passive"))
      (node (ref "R2") (pin "2") (pinfunction "2_2") (pintype "passive"))
    )
    (net (code "45") (name "Net-(OK2-C)") (class "Default")
      (node (ref "OK2") (pin "3") (pinfunction "C_3") (pintype "passive"))
      (node (ref "R3") (pin "2") (pinfunction "2_2") (pintype "passive"))
    )
    (net (code "46") (name "Net-(STEPPERDRIVER-MOT-1A)") (class "Default")
      (node (ref "STEPPERDRIVER") (pin "1A") (pinfunction "MOT-1A_1A") (pintype "power_in"))
      (node (ref "XMS2") (pin "1") (pinfunction "1_1") (pintype "passive"))
    )
    (net (code "47") (name "Net-(STEPPERDRIVER-MOT-1B)") (class "Default")
      (node (ref "STEPPERDRIVER") (pin "1B") (pinfunction "MOT-1B_1B") (pintype "power_in"))
      (node (ref "XMS2") (pin "2") (pinfunction "2_2") (pintype "passive"))
    )
    (net (code "48") (name "Net-(STEPPERDRIVER-MOT-2A)") (class "Default")
      (node (ref "STEPPERDRIVER") (pin "2A") (pinfunction "MOT-2A_2A") (pintype "power_in"))
      (node (ref "XMS1") (pin "2") (pinfunction "2_2") (pintype "passive"))
    )
    (net (code "49") (name "Net-(STEPPERDRIVER-MOT-2B)") (class "Default")
      (node (ref "STEPPERDRIVER") (pin "2B") (pinfunction "MOT-2B_2B") (pintype "power_in"))
      (node (ref "XMS1") (pin "1") (pinfunction "1_1") (pintype "passive"))
    )
    (net (code "50") (name "Net-(STEPPERDRIVER-~{RESET})") (class "Default")
      (node (ref "STEPPERDRIVER") (pin "!RST") (pinfunction "~{RESET}_!RST") (pintype "input"))
      (node (ref "STEPPERDRIVER") (pin "!SLP") (pinfunction "~{SLEEP}_!SLP") (pintype "input"))
    )
    (net (code "51") (name "Net-(STEPPERDRIVER1-MOT-1A)") (class "Default")
      (node (ref "STEPPERDRIVER1") (pin "1A") (pinfunction "MOT-1A_1A") (pintype "power_in"))
      (node (ref "XMS4") (pin "1") (pinfunction "1_1") (pintype "passive"))
    )
    (net (code "52") (name "Net-(STEPPERDRIVER1-MOT-1B)") (class "Default")
      (node (ref "STEPPERDRIVER1") (pin "1B") (pinfunction "MOT-1B_1B") (pintype "power_in"))
      (node (ref "XMS4") (pin "2") (pinfunction "2_2") (pintype "passive"))
    )
    (net (code "53") (name "Net-(STEPPERDRIVER1-MOT-2A)") (class "Default")
      (node (ref "STEPPERDRIVER1") (pin "2A") (pinfunction "MOT-2A_2A") (pintype "power_in"))
      (node (ref "XMS3") (pin "2") (pinfunction "2_2") (pintype "passive"))
    )
    (net (code "54") (name "Net-(STEPPERDRIVER1-MOT-2B)") (class "Default")
      (node (ref "STEPPERDRIVER1") (pin "2B") (pinfunction "MOT-2B_2B") (pintype "power_in"))
      (node (ref "XMS3") (pin "1") (pinfunction "1_1") (pintype "passive"))
    )
    (net (code "55") (name "Net-(STEPPERDRIVER1-~{RESET})") (class "Default")
      (node (ref "STEPPERDRIVER1") (pin "!RST") (pinfunction "~{RESET}_!RST") (pintype "input"))
      (node (ref "STEPPERDRIVER1") (pin "!SLP") (pinfunction "~{SLEEP}_!SLP") (pintype "input"))
    )
    (net (code "56") (name "Net-(STEPPERDRIVER2-MOT-1A)") (class "Default")
      (node (ref "STEPPERDRIVER2") (pin "1A") (pinfunction "MOT-1A_1A") (pintype "power_in"))
      (node (ref "XMS6") (pin "1") (pinfunction "1_1") (pintype "passive"))
    )
    (net (code "57") (name "Net-(STEPPERDRIVER2-MOT-1B)") (class "Default")
      (node (ref "STEPPERDRIVER2") (pin "1B") (pinfunction "MOT-1B_1B") (pintype "power_in"))
      (node (ref "XMS6") (pin "2") (pinfunction "2_2") (pintype "passive"))
    )
    (net (code "58") (name "Net-(STEPPERDRIVER2-MOT-2A)") (class "Default")
      (node (ref "STEPPERDRIVER2") (pin "2A") (pinfunction "MOT-2A_2A") (pintype "power_in"))
      (node (ref "XMS5") (pin "2") (pinfunction "2_2") (pintype "passive"))
    )
    (net (code "59") (name "Net-(STEPPERDRIVER2-MOT-2B)") (class "Default")
      (node (ref "STEPPERDRIVER2") (pin "2B") (pinfunction "MOT-2B_2B") (pintype "power_in"))
      (node (ref "XMS5") (pin "1") (pinfunction "1_1") (pintype "passive"))
    )
    (net (code "60") (name "Net-(STEPPERDRIVER2-~{RESET})") (class "Default")
      (node (ref "STEPPERDRIVER2") (pin "!RST") (pinfunction "~{RESET}_!RST") (pintype "input"))
      (node (ref "STEPPERDRIVER2") (pin "!SLP") (pinfunction "~{SLEEP}_!SLP") (pintype "input"))
    )
    (net (code "61") (name "Net-(STEPPERDRIVER3-MOT-1A)") (class "Default")
      (node (ref "STEPPERDRIVER3") (pin "1A") (pinfunction "MOT-1A_1A") (pintype "power_in"))
      (node (ref "XMS8") (pin "1") (pinfunction "1_1") (pintype "passive"))
    )
    (net (code "62") (name "Net-(STEPPERDRIVER3-MOT-1B)") (class "Default")
      (node (ref "STEPPERDRIVER3") (pin "1B") (pinfunction "MOT-1B_1B") (pintype "power_in"))
      (node (ref "XMS8") (pin "2") (pinfunction "2_2") (pintype "passive"))
    )
    (net (code "63") (name "Net-(STEPPERDRIVER3-MOT-2A)") (class "Default")
      (node (ref "STEPPERDRIVER3") (pin "2A") (pinfunction "MOT-2A_2A") (pintype "power_in"))
      (node (ref "XMS7") (pin "2") (pinfunction "2_2") (pintype "passive"))
    )
    (net (code "64") (name "Net-(STEPPERDRIVER3-MOT-2B)") (class "Default")
      (node (ref "STEPPERDRIVER3") (pin "2B") (pinfunction "MOT-2B_2B") (pintype "power_in"))
      (node (ref "XMS7") (pin "1") (pinfunction "1_1") (pintype "passive"))
    )
    (net (code "65") (name "Net-(STEPPERDRIVER3-~{RESET})") (class "Default")
      (node (ref "STEPPERDRIVER3") (pin "!RST") (pinfunction "~{RESET}_!RST") (pintype "input"))
      (node (ref "STEPPERDRIVER3") (pin "!SLP") (pinfunction "~{SLEEP}_!SLP") (pintype "input"))
    )
    (net (code "66") (name "USB_GND") (class "Default")
      (node (ref "C14") (pin "2") (pinfunction "2_2") (pintype "passive"))
      (node (ref "OK1") (pin "5") (pinfunction "GND_5") (pintype "passive"))
      (node (ref "USB_TTL") (pin "1") (pinfunction "1_1") (pintype "passive"))
      (node (ref "USB_TTL") (pin "2") (pinfunction "2_2") (pintype "passive"))
    )
    (net (code "67") (name "unconnected-(ATMEGA328-PC5(ADC5{slash}SCL)-Pad28)") (class "Default")
      (node (ref "ATMEGA328") (pin "28") (pinfunction "PC5(ADC5/SCL)_28") (pintype "bidirectional"))
    )
    (net (code "68") (name "unconnected-(USB_TTL-Pad6)") (class "Default")
      (node (ref "USB_TTL") (pin "6") (pinfunction "6_6") (pintype "passive"))
    )
  )
)
